# esp32_mcu.net
KiCad netlist of a schematic drawn in Altium Designer
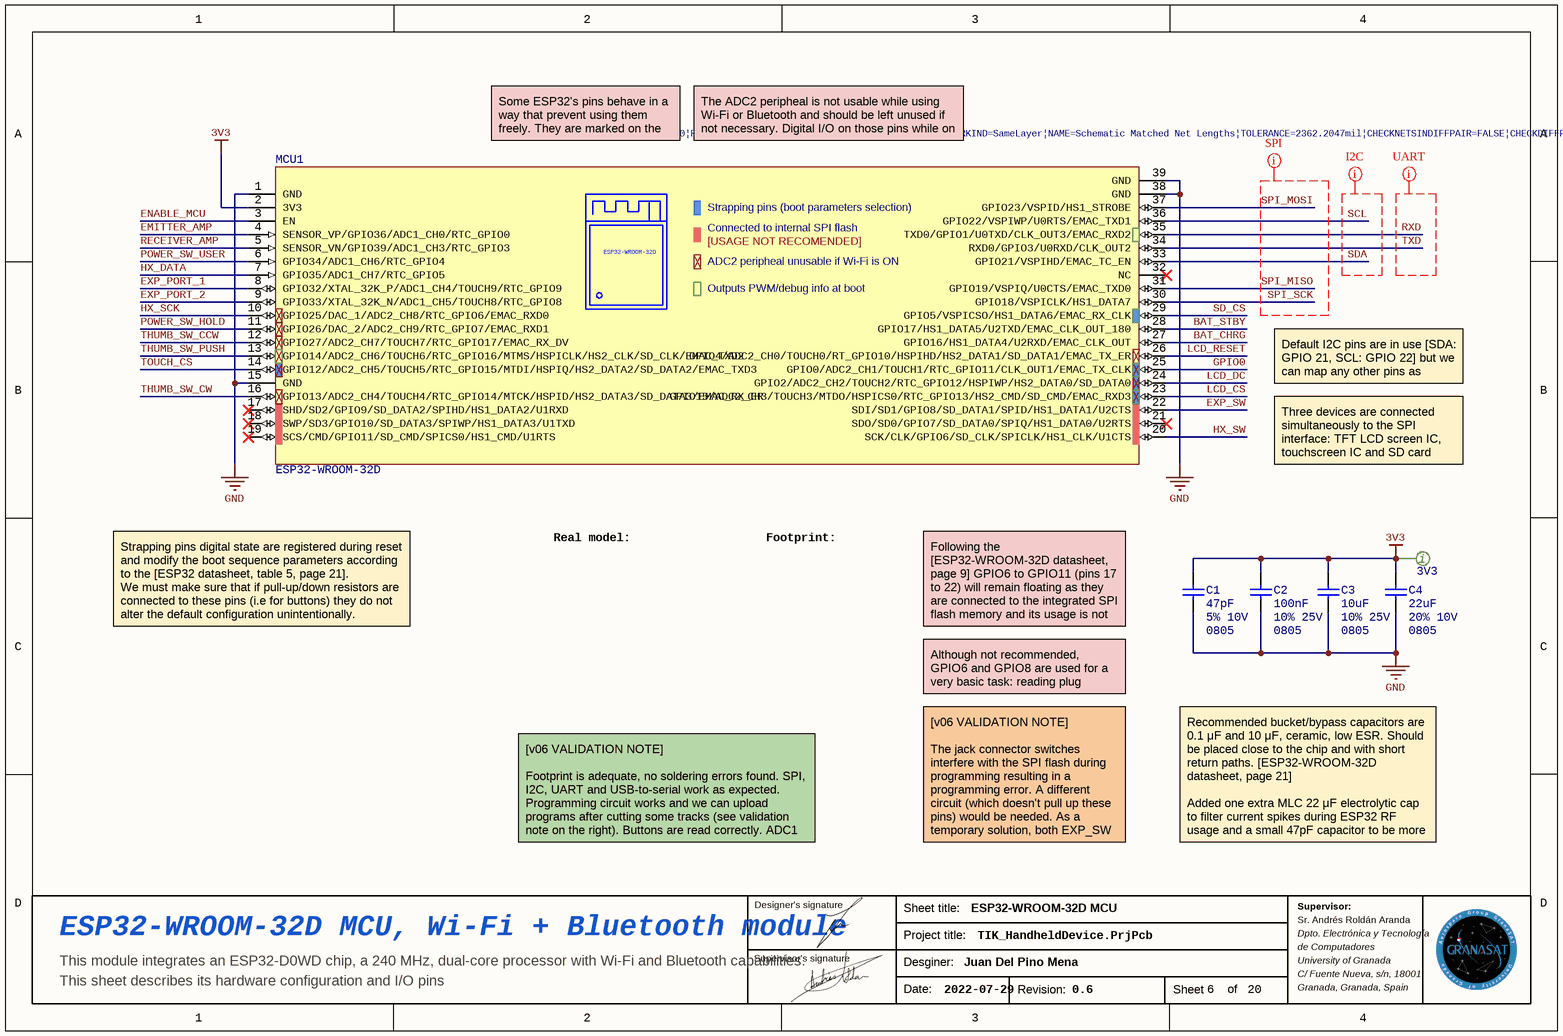
[diagram p0: esp32_mcu.SchDoc]

(export (version "E")
  (design (tool "Eeschema 10.0.6"))
  (components
    (comp (ref "3V3")
      (value "Test Point Pad dual sided")
      (footprint "TEST POINT PAD")
      (description "Test point - PCB Pad dual sided")
      (libsource (lib "tik_handheld_schlib") (part "Test Point Pad dual sided"))
    )
    (comp (ref "C1")
      (value "47pF")
      (footprint "CAP 0805_2012")
      (description "Ceramic cap size 0805")
      (fields
        (field (name "TOLERANCE") "5% 10V")
        (field (name "PACKAGEDESCRIPTION") "0805")
        (field (name "Comment") "Cap_cer_0805")
      )
      (libsource (lib "tik_handheld_schlib") (part "Cap_cer_0805_47pF_5%"))
    )
    (comp (ref "C2")
      (value "100nF")
      (footprint "CAP 0805_2012")
      (description "Ceramic cap size 0805")
      (fields
        (field (name "TOLERANCE") "10% 25V")
        (field (name "PACKAGEDESCRIPTION") "0805")
        (field (name "Comment") "Cap_cer_0805")
      )
      (libsource (lib "tik_handheld_schlib") (part "Cap_cer_0805_100nF_10%"))
    )
    (comp (ref "C3")
      (value "10uF")
      (footprint "CAP 0805_2012")
      (description "Ceramic cap size 0805")
      (fields
        (field (name "TOLERANCE") "10% 25V")
        (field (name "PACKAGEDESCRIPTION") "0805")
        (field (name "Comment") "Cap_cer_0805")
      )
      (libsource (lib "tik_handheld_schlib") (part "Cap_cer_0805_10uF_10%"))
    )
    (comp (ref "C4")
      (value "22uF")
      (footprint "CAP 0805_2012")
      (description "Ceramic cap size 0805 CC0805MKX5R6BB226 Yageo MLCC 22uF 10V 20% X5R")
      (fields
        (field (name "TOLERANCE") "20% 10V")
        (field (name "PACKAGEDESCRIPTION") "0805")
        (field (name "Comment") "Cap_cer_0805")
      )
      (libsource (lib "tik_handheld_schlib") (part "Cap_cer_0805_22uF_20%"))
    )
    (comp (ref "MCU1")
      (value "MCU ESP32-WROOM-32D")
      (footprint "MODULE_ESP32-WROOM-32")
      (fields
        (field (name "MF") "Espressif Systems")
        (field (name "MP") "ESP32-WROOM-32D")
        (field (name "PART") "ESP32-WROOM-32D")
      )
      (libsource (lib "tik_handheld_schlib") (part "MCU ESP32-WROOM-32D"))
    )
  )
  (nets
    (net (code "1") (name "/BAT_CHRG") (class "Default")
      (node (ref "MCU1") (pin "27") (pinfunction "GPIO16/HS1_DATA4/U2RXD/EMAC_CLK_OUT_27") (pintype "bidirectional"))
    )
    (net (code "2") (name "/BAT_STBY") (class "Default")
      (node (ref "MCU1") (pin "28") (pinfunction "GPIO17/HS1_DATA5/U2TXD/EMAC_CLK_OUT_180_28") (pintype "bidirectional"))
    )
    (net (code "3") (name "/EMITTER_AMP") (class "Default")
      (node (ref "MCU1") (pin "4") (pinfunction "SENSOR_VP/GPIO36/ADC1_CH0/RTC_GPIO0_4") (pintype "input"))
    )
    (net (code "4") (name "/ENABLE_MCU") (class "Default")
      (node (ref "MCU1") (pin "3") (pinfunction "EN_3") (pintype "power_in"))
    )
    (net (code "5") (name "/EXP_PORT_1") (class "Default")
      (node (ref "MCU1") (pin "8") (pinfunction "GPIO32/XTAL_32K_P/ADC1_CH4/TOUCH9/RTC_GPIO9_8") (pintype "bidirectional"))
    )
    (net (code "6") (name "/EXP_PORT_2") (class "Default")
      (node (ref "MCU1") (pin "9") (pinfunction "GPIO33/XTAL_32K_N/ADC1_CH5/TOUCH8/RTC_GPIO8_9") (pintype "bidirectional"))
    )
    (net (code "7") (name "/EXP_SW") (class "Default")
      (node (ref "MCU1") (pin "22") (pinfunction "SDI/SD1/GPIO8/SD_DATA1/SPID/HS1_DATA1/U2CTS_22") (pintype "bidirectional"))
    )
    (net (code "8") (name "/GPIO0") (class "Default")
      (node (ref "MCU1") (pin "25") (pinfunction "GPIO0/ADC2_CH1/TOUCH1/RTC_GPIO11/CLK_OUT1/EMAC_TX_CLK_25") (pintype "bidirectional"))
    )
    (net (code "9") (name "/HX_DATA") (class "Default")
      (node (ref "MCU1") (pin "7") (pinfunction "GPIO35/ADC1_CH7/RTC_GPIO5_7") (pintype "input"))
    )
    (net (code "10") (name "/HX_SCK") (class "Default")
      (node (ref "MCU1") (pin "10") (pinfunction "GPIO25/DAC_1/ADC2_CH8/RTC_GPIO6/EMAC_RXD0_10") (pintype "bidirectional"))
    )
    (net (code "11") (name "/HX_SW") (class "Default")
      (node (ref "MCU1") (pin "20") (pinfunction "SCK/CLK/GPIO6/SD_CLK/SPICLK/HS1_CLK/U1CTS_20") (pintype "bidirectional"))
    )
    (net (code "12") (name "/LCD_CS") (class "Default")
      (node (ref "MCU1") (pin "23") (pinfunction "GPIO15/ADC2_CH3/TOUCH3/MTDO/HSPICS0/RTC_GPIO13/HS2_CMD/SD_CMD/EMAC_RXD3_23") (pintype "bidirectional"))
    )
    (net (code "13") (name "/LCD_DC") (class "Default")
      (node (ref "MCU1") (pin "24") (pinfunction "GPIO2/ADC2_CH2/TOUCH2/RTC_GPIO12/HSPIWP/HS2_DATA0/SD_DATA0_24") (pintype "bidirectional"))
    )
    (net (code "14") (name "/LCD_RESET") (class "Default")
      (node (ref "MCU1") (pin "26") (pinfunction "GPIO4/ADC2_CH0/TOUCH0/RT_GPIO10/HSPIHD/HS2_DATA1/SD_DATA1/EMAC_TX_ER_26") (pintype "bidirectional"))
    )
    (net (code "15") (name "/POWER_SW_HOLD") (class "Default")
      (node (ref "MCU1") (pin "11") (pinfunction "GPIO26/DAC_2/ADC2_CH9/RTC_GPIO7/EMAC_RXD1_11") (pintype "bidirectional"))
    )
    (net (code "16") (name "/POWER_SW_USER") (class "Default")
      (node (ref "MCU1") (pin "6") (pinfunction "GPIO34/ADC1_CH6/RTC_GPIO4_6") (pintype "input"))
    )
    (net (code "17") (name "/RECEIVER_AMP") (class "Default")
      (node (ref "MCU1") (pin "5") (pinfunction "SENSOR_VN/GPIO39/ADC1_CH3/RTC_GPIO3_5") (pintype "input"))
    )
    (net (code "18") (name "/RXD") (class "Default")
      (node (ref "MCU1") (pin "35") (pinfunction "TXD0/GPIO1/U0TXD/CLK_OUT3/EMAC_RXD2_35") (pintype "bidirectional"))
    )
    (net (code "19") (name "/SCL") (class "Default")
      (node (ref "MCU1") (pin "36") (pinfunction "GPIO22/VSPIWP/U0RTS/EMAC_TXD1_36") (pintype "bidirectional"))
    )
    (net (code "20") (name "/SDA") (class "Default")
      (node (ref "MCU1") (pin "33") (pinfunction "GPIO21/VSPIHD/EMAC_TC_EN_33") (pintype "bidirectional"))
    )
    (net (code "21") (name "/SD_CS") (class "Default")
      (node (ref "MCU1") (pin "29") (pinfunction "GPIO5/VSPICSO/HS1_DATA6/EMAC_RX_CLK_29") (pintype "bidirectional"))
    )
    (net (code "22") (name "/SPI_MISO") (class "Default")
      (node (ref "MCU1") (pin "31") (pinfunction "GPIO19/VSPIQ/U0CTS/EMAC_TXD0_31") (pintype "bidirectional"))
    )
    (net (code "23") (name "/SPI_MOSI") (class "Default")
      (node (ref "MCU1") (pin "37") (pinfunction "GPIO23/VSPID/HS1_STROBE_37") (pintype "bidirectional"))
    )
    (net (code "24") (name "/SPI_SCK") (class "Default")
      (node (ref "MCU1") (pin "30") (pinfunction "GPIO18/VSPICLK/HS1_DATA7_30") (pintype "bidirectional"))
    )
    (net (code "25") (name "/THUMB_SW_CCW") (class "Default")
      (node (ref "MCU1") (pin "12") (pinfunction "GPIO27/ADC2_CH7/TOUCH7/RTC_GPIO17/EMAC_RX_DV_12") (pintype "bidirectional"))
    )
    (net (code "26") (name "/THUMB_SW_CW") (class "Default")
      (node (ref "MCU1") (pin "16") (pinfunction "GPIO13/ADC2_CH4/TOUCH4/RTC_GPIO14/MTCK/HSPID/HS2_DATA3/SD_DATA3/EMAC_RX_ER_16") (pintype "bidirectional"))
    )
    (net (code "27") (name "/THUMB_SW_PUSH") (class "Default")
      (node (ref "MCU1") (pin "13") (pinfunction "GPIO14/ADC2_CH6/TOUCH6/RTC_GPIO16/MTMS/HSPICLK/HS2_CLK/SD_CLK/EMAC_TXD2_13") (pintype "bidirectional"))
    )
    (net (code "28") (name "/TOUCH_CS") (class "Default")
      (node (ref "MCU1") (pin "14") (pinfunction "GPIO12/ADC2_CH5/TOUCH5/RTC_GPIO15/MTDI/HSPIQ/HS2_DATA2/SD_DATA2/EMAC_TXD3_14") (pintype "bidirectional"))
    )
    (net (code "29") (name "/TXD") (class "Default")
      (node (ref "MCU1") (pin "34") (pinfunction "RXD0/GPIO3/U0RXD/CLK_OUT2_34") (pintype "bidirectional"))
    )
    (net (code "30") (name "3V3") (class "Default")
      (node (ref "3V3") (pin "1") (pinfunction "1_1") (pintype "passive"))
      (node (ref "C1") (pin "2") (pinfunction "2_2") (pintype "passive"))
      (node (ref "C2") (pin "2") (pinfunction "2_2") (pintype "passive"))
      (node (ref "C3") (pin "2") (pinfunction "2_2") (pintype "passive"))
      (node (ref "C4") (pin "2") (pinfunction "2_2") (pintype "passive"))
      (node (ref "MCU1") (pin "2") (pinfunction "3V3_2") (pintype "power_in"))
    )
    (net (code "31") (name "GND") (class "Default")
      (node (ref "C1") (pin "1") (pinfunction "1_1") (pintype "passive"))
      (node (ref "C2") (pin "1") (pinfunction "1_1") (pintype "passive"))
      (node (ref "C3") (pin "1") (pinfunction "1_1") (pintype "passive"))
      (node (ref "C4") (pin "1") (pinfunction "1_1") (pintype "passive"))
      (node (ref "MCU1") (pin "1") (pinfunction "GND_1") (pintype "power_in"))
      (node (ref "MCU1") (pin "15") (pinfunction "GND_15") (pintype "power_in"))
      (node (ref "MCU1") (pin "38") (pinfunction "GND_38") (pintype "power_in"))
      (node (ref "MCU1") (pin "39") (pinfunction "GND_39") (pintype "power_in"))
    )
    (net (code "32") (name "unconnected-(MCU1-NC-Pad32)") (class "Default")
      (node (ref "MCU1") (pin "32") (pinfunction "NC_32") (pintype "passive+no_connect"))
    )
    (net (code "33") (name "unconnected-(MCU1-SCS{slash}CMD{slash}GPIO11{slash}SD_CMD{slash}SPICS0{slash}HS1_CMD{slash}U1RTS-Pad19)") (class "Default")
      (node (ref "MCU1") (pin "19") (pinfunction "SCS/CMD/GPIO11/SD_CMD/SPICS0/HS1_CMD/U1RTS_19") (pintype "bidirectional+no_connect"))
    )
    (net (code "34") (name "unconnected-(MCU1-SDO{slash}SD0{slash}GPIO7{slash}SD_DATA0{slash}SPIQ{slash}HS1_DATA0{slash}U2RTS-Pad21)") (class "Default")
      (node (ref "MCU1") (pin "21") (pinfunction "SDO/SD0/GPIO7/SD_DATA0/SPIQ/HS1_DATA0/U2RTS_21") (pintype "bidirectional+no_connect"))
    )
    (net (code "35") (name "unconnected-(MCU1-SHD{slash}SD2{slash}GPIO9{slash}SD_DATA2{slash}SPIHD{slash}HS1_DATA2{slash}U1RXD-Pad17)") (class "Default")
      (node (ref "MCU1") (pin "17") (pinfunction "SHD/SD2/GPIO9/SD_DATA2/SPIHD/HS1_DATA2/U1RXD_17") (pintype "bidirectional+no_connect"))
    )
    (net (code "36") (name "unconnected-(MCU1-SWP{slash}SD3{slash}GPIO10{slash}SD_DATA3{slash}SPIWP{slash}HS1_DATA3{slash}U1TXD-Pad18)") (class "Default")
      (node (ref "MCU1") (pin "18") (pinfunction "SWP/SD3/GPIO10/SD_DATA3/SPIWP/HS1_DATA3/U1TXD_18") (pintype "bidirectional+no_connect"))
    )
  )
)
